# ATECC608A_Crypto_Authentication.net
KiCad netlist of a schematic drawn in Altium Designer
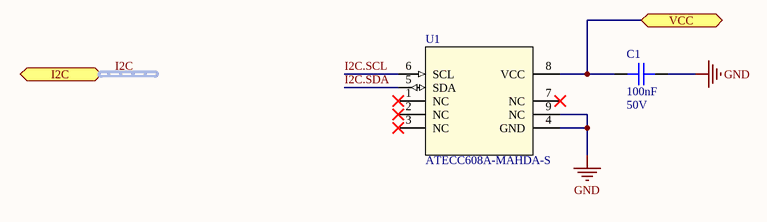
[diagram p0: ATECC608A_Crypto_Authentication.SchDoc]

(export (version "E")
  (design (tool "Eeschema 10.0.6"))
  (components
    (comp (ref "C1")
      (value "CAP CER 0.1UF 50V X7R 0402")
      (footprint "C0402")
      (description "0.1µF ±10% 50V Ceramic Capacitor X7R 0402 (1005 Metric)")
      (fields
        (field (name "MANUFACTURER") "TDK")
        (field (name "MANUFACTURER PART NUMBER") "CGA2B3X7R1H104K050BB")
        (field (name "CAPACITANCE") "100nF")
        (field (name "VOLTAGE") "50V")
      )
      (libsource (lib "capacitors_smd") (part "CAP CER 0.1UF 50V X7R 0402"))
    )
    (comp (ref "U1")
      (value "ATECC608A-MAHDA-S")
      (footprint "UDFN8_2x3MC_MCH")
      (description "Authentication Chip 8-UDFN (2x3)")
      (fields (field (name "MANUFACTURER") "Microchip"))
      (libsource (lib "BLDC_Motor_Driver") (part "IC ATECC608A-MAHDA-S AUTHENTICATION CHIP 8UDFN"))
    )
  )
  (nets
    (net (code "2") (name "/I2C.SCL") (class "Default")
      (node (ref "U1") (pin "6") (pinfunction "SCL_6") (pintype "input"))
    )
    (net (code "3") (name "/I2C.SDA") (class "Default")
      (node (ref "U1") (pin "5") (pinfunction "SDA_5") (pintype "bidirectional"))
    )
    (net (code "4") (name "/VCC") (class "Default")
      (node (ref "C1") (pin "1") (pinfunction "1_1") (pintype "passive"))
      (node (ref "U1") (pin "8") (pinfunction "VCC_8") (pintype "power_in"))
    )
    (net (code "6") (name "GND") (class "Default")
      (node (ref "C1") (pin "2") (pinfunction "2_2") (pintype "passive"))
      (node (ref "U1") (pin "4") (pinfunction "GND_4") (pintype "power_in"))
      (node (ref "U1") (pin "9") (pinfunction "NC_9") (pintype "passive"))
    )
    (net (code "7") (name "unconnected-(U1-NC-Pad1)") (class "Default")
      (node (ref "U1") (pin "1") (pinfunction "NC_1") (pintype "passive+no_connect"))
    )
    (net (code "8") (name "unconnected-(U1-NC-Pad2)") (class "Default")
      (node (ref "U1") (pin "2") (pinfunction "NC_2") (pintype "passive+no_connect"))
    )
    (net (code "9") (name "unconnected-(U1-NC-Pad3)") (class "Default")
      (node (ref "U1") (pin "3") (pinfunction "NC_3") (pintype "passive+no_connect"))
    )
    (net (code "10") (name "unconnected-(U1-NC-Pad7)") (class "Default")
      (node (ref "U1") (pin "7") (pinfunction "NC_7") (pintype "passive+no_connect"))
    )
  )
)
